# TemperatureSensor.net
KiCad netlist of a schematic drawn in EAGLE
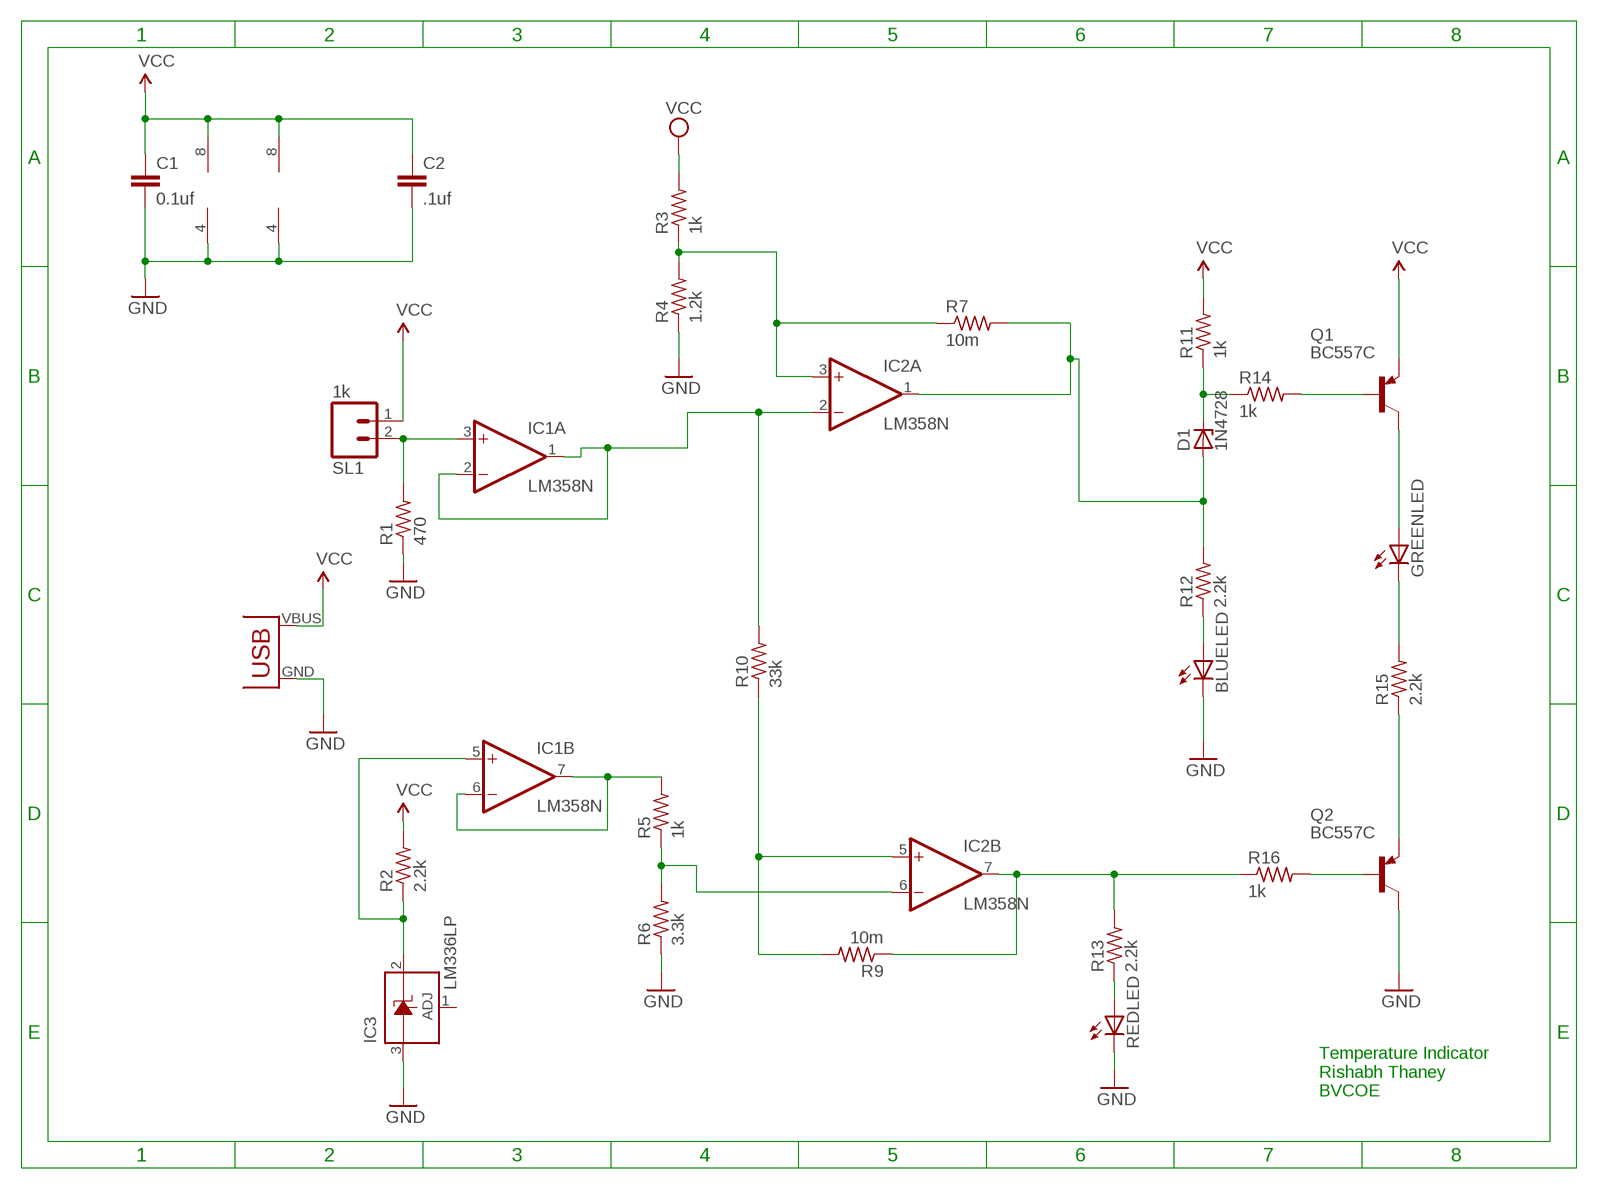
[diagram p0: schematic, sheet 1]

(export (version "E")
  (design (tool "Eeschema 10.0.6"))
  (components
    (comp (ref "BLUELED")
      (value "LED5MM")
      (footprint "eagle-import:LED5MM")
      (libsource (lib "eagle-import") (part "LED5MM"))
    )
    (comp (ref "C1")
      (value "0.1uf")
      (footprint "eagle-import:C025-024X044")
      (libsource (lib "eagle-import") (part "C-EU025-024X044"))
    )
    (comp (ref "C2")
      (value ".1uf")
      (footprint "eagle-import:C025-024X044")
      (libsource (lib "eagle-import") (part "C-EU025-024X044"))
    )
    (comp (ref "D1")
      (value "1N4728")
      (footprint "eagle-import:DO41Z10")
      (libsource (lib "eagle-import") (part "1N4728"))
    )
    (comp (ref "GREENLED")
      (value "LED5MM")
      (footprint "eagle-import:LED5MM")
      (libsource (lib "eagle-import") (part "LED5MM"))
    )
    (comp (ref "IC1")
      (value "LM358N")
      (footprint "eagle-import:DIL08")
      (libsource (lib "eagle-import") (part "LM358N"))
    )
    (comp (ref "IC2")
      (value "LM358N")
      (footprint "eagle-import:DIL08")
      (libsource (lib "eagle-import") (part "LM358N"))
    )
    (comp (ref "IC3")
      (value "LM336LP")
      (footprint "eagle-import:TO92")
      (libsource (lib "eagle-import") (part "LM336LP"))
    )
    (comp (ref "Q1")
      (value "BC557C")
      (footprint "eagle-import:TO92-EBC")
      (libsource (lib "eagle-import") (part "BC557C"))
    )
    (comp (ref "Q2")
      (value "BC557C")
      (footprint "eagle-import:TO92-EBC")
      (libsource (lib "eagle-import") (part "BC557C"))
    )
    (comp (ref "R1")
      (value "470")
      (footprint "eagle-import:0204_7")
      (libsource (lib "eagle-import") (part "R-US_0204/7"))
    )
    (comp (ref "R2")
      (value "2.2k")
      (footprint "eagle-import:0204_7")
      (libsource (lib "eagle-import") (part "R-US_0204/7"))
    )
    (comp (ref "R3")
      (value "1k")
      (footprint "eagle-import:0204_7")
      (libsource (lib "eagle-import") (part "R-US_0204/7"))
    )
    (comp (ref "R4")
      (value "1.2k")
      (footprint "eagle-import:0204_7")
      (libsource (lib "eagle-import") (part "R-US_0204/7"))
    )
    (comp (ref "R5")
      (value "1k")
      (footprint "eagle-import:0204_7")
      (libsource (lib "eagle-import") (part "R-US_0204/7"))
    )
    (comp (ref "R6")
      (value "3.3k")
      (footprint "eagle-import:0204_7")
      (libsource (lib "eagle-import") (part "R-US_0204/7"))
    )
    (comp (ref "R7")
      (value "10m")
      (footprint "eagle-import:0204_7")
      (libsource (lib "eagle-import") (part "R-US_0204/7"))
    )
    (comp (ref "R9")
      (value "10m")
      (footprint "eagle-import:0204_7")
      (libsource (lib "eagle-import") (part "R-US_0204/7"))
    )
    (comp (ref "R10")
      (value "33k")
      (footprint "eagle-import:0204_7")
      (libsource (lib "eagle-import") (part "R-US_0204/7"))
    )
    (comp (ref "R11")
      (value "1k")
      (footprint "eagle-import:0204_7")
      (libsource (lib "eagle-import") (part "R-US_0204/7"))
    )
    (comp (ref "R12")
      (value "2.2k")
      (footprint "eagle-import:0204_7")
      (libsource (lib "eagle-import") (part "R-US_0204/7"))
    )
    (comp (ref "R13")
      (value "2.2k")
      (footprint "eagle-import:0204_7")
      (libsource (lib "eagle-import") (part "R-US_0204/7"))
    )
    (comp (ref "R14")
      (value "1k")
      (footprint "eagle-import:0204_7")
      (libsource (lib "eagle-import") (part "R-US_0204/7"))
    )
    (comp (ref "R15")
      (value "2.2k")
      (footprint "eagle-import:0204_7")
      (libsource (lib "eagle-import") (part "R-US_0204/7"))
    )
    (comp (ref "R16")
      (value "1k")
      (footprint "eagle-import:0204_7")
      (libsource (lib "eagle-import") (part "R-US_0204/7"))
    )
    (comp (ref "REDLED")
      (value "LED5MM")
      (footprint "eagle-import:LED5MM")
      (libsource (lib "eagle-import") (part "LED5MM"))
    )
    (comp (ref "SL1")
      (value "1k")
      (footprint "eagle-import:02P")
      (libsource (lib "eagle-import") (part "M02"))
    )
    (comp (ref "U$1")
      (value "USB(POWER)")
      (footprint "eagle-import:USB(POWER)")
      (libsource (lib "eagle-import") (part "USB(POWER)"))
    )
  )
  (nets
    (net (code "1") (name "GND") (class "Default")
      (node (ref "BLUELED") (pin "K") (pinfunction "C_K") (pintype "passive"))
      (node (ref "C1") (pin "2") (pinfunction "2_2") (pintype "passive"))
      (node (ref "C2") (pin "2") (pinfunction "2_2") (pintype "passive"))
      (node (ref "IC1") (pin "4") (pinfunction "V-_4") (pintype "power_in"))
      (node (ref "IC2") (pin "4") (pinfunction "V-_4") (pintype "power_in"))
      (node (ref "IC3") (pin "3") (pinfunction "A_3") (pintype "input"))
      (node (ref "Q2") (pin "C") (pinfunction "C_C") (pintype "passive"))
      (node (ref "R1") (pin "1") (pinfunction "1_1") (pintype "passive"))
      (node (ref "R4") (pin "1") (pinfunction "1_1") (pintype "passive"))
      (node (ref "R6") (pin "1") (pinfunction "1_1") (pintype "passive"))
      (node (ref "REDLED") (pin "K") (pinfunction "C_K") (pintype "passive"))
      (node (ref "U$1") (pin "GND") (pinfunction "GND_GND") (pintype "power_in"))
    )
    (net (code "2") (name "Net-(BLUELED-PadA)") (class "Default")
      (node (ref "BLUELED") (pin "A") (pinfunction "A_A") (pintype "passive"))
      (node (ref "R12") (pin "1") (pinfunction "1_1") (pintype "passive"))
    )
    (net (code "3") (name "Net-(D1-PadC)") (class "Default")
      (node (ref "D1") (pin "C") (pinfunction "C_C") (pintype "passive"))
      (node (ref "R11") (pin "1") (pinfunction "1_1") (pintype "passive"))
      (node (ref "R14") (pin "1") (pinfunction "1_1") (pintype "passive"))
    )
    (net (code "4") (name "Net-(GREENLED-C)") (class "Default")
      (node (ref "GREENLED") (pin "K") (pinfunction "C_K") (pintype "passive"))
      (node (ref "R15") (pin "2") (pinfunction "2_2") (pintype "passive"))
    )
    (net (code "5") (name "Net-(GREENLED-PadA)") (class "Default")
      (node (ref "GREENLED") (pin "A") (pinfunction "A_A") (pintype "passive"))
      (node (ref "Q1") (pin "C") (pinfunction "C_C") (pintype "passive"))
    )
    (net (code "6") (name "Net-(IC1A-+IN)") (class "Default")
      (node (ref "IC1") (pin "3") (pinfunction "+IN_3") (pintype "input"))
      (node (ref "R1") (pin "2") (pinfunction "2_2") (pintype "passive"))
      (node (ref "SL1") (pin "2") (pinfunction "2_2") (pintype "passive"))
    )
    (net (code "7") (name "Net-(IC1A--IN)") (class "Default")
      (node (ref "IC1") (pin "1") (pinfunction "OUT_1") (pintype "output"))
      (node (ref "IC1") (pin "2") (pinfunction "-IN_2") (pintype "input"))
      (node (ref "IC2") (pin "2") (pinfunction "-IN_2") (pintype "input"))
      (node (ref "R10") (pin "2") (pinfunction "2_2") (pintype "passive"))
    )
    (net (code "8") (name "Net-(IC1B-+IN)") (class "Default")
      (node (ref "IC1") (pin "5") (pinfunction "+IN_5") (pintype "input"))
      (node (ref "IC3") (pin "2") (pinfunction "C_2") (pintype "passive"))
      (node (ref "R2") (pin "1") (pinfunction "1_1") (pintype "passive"))
    )
    (net (code "9") (name "Net-(IC1B--IN)") (class "Default")
      (node (ref "IC1") (pin "6") (pinfunction "-IN_6") (pintype "input"))
      (node (ref "IC1") (pin "7") (pinfunction "OUT_7") (pintype "output"))
      (node (ref "R5") (pin "2") (pinfunction "2_2") (pintype "passive"))
    )
    (net (code "10") (name "Net-(IC2A-+IN)") (class "Default")
      (node (ref "IC2") (pin "3") (pinfunction "+IN_3") (pintype "input"))
      (node (ref "R3") (pin "1") (pinfunction "1_1") (pintype "passive"))
      (node (ref "R4") (pin "2") (pinfunction "2_2") (pintype "passive"))
      (node (ref "R7") (pin "1") (pinfunction "1_1") (pintype "passive"))
    )
    (net (code "11") (name "Net-(IC2A-OUT)") (class "Default")
      (node (ref "D1") (pin "A") (pinfunction "A_A") (pintype "passive"))
      (node (ref "IC2") (pin "1") (pinfunction "OUT_1") (pintype "output"))
      (node (ref "R12") (pin "2") (pinfunction "2_2") (pintype "passive"))
      (node (ref "R7") (pin "2") (pinfunction "2_2") (pintype "passive"))
    )
    (net (code "12") (name "Net-(IC2B-+IN)") (class "Default")
      (node (ref "IC2") (pin "5") (pinfunction "+IN_5") (pintype "input"))
      (node (ref "R10") (pin "1") (pinfunction "1_1") (pintype "passive"))
      (node (ref "R9") (pin "2") (pinfunction "2_2") (pintype "passive"))
    )
    (net (code "13") (name "Net-(IC2B--IN)") (class "Default")
      (node (ref "IC2") (pin "6") (pinfunction "-IN_6") (pintype "input"))
      (node (ref "R5") (pin "1") (pinfunction "1_1") (pintype "passive"))
      (node (ref "R6") (pin "2") (pinfunction "2_2") (pintype "passive"))
    )
    (net (code "14") (name "Net-(IC2B-OUT)") (class "Default")
      (node (ref "IC2") (pin "7") (pinfunction "OUT_7") (pintype "output"))
      (node (ref "R13") (pin "2") (pinfunction "2_2") (pintype "passive"))
      (node (ref "R16") (pin "1") (pinfunction "1_1") (pintype "passive"))
      (node (ref "R9") (pin "1") (pinfunction "1_1") (pintype "passive"))
    )
    (net (code "15") (name "Net-(Q1-PadB)") (class "Default")
      (node (ref "Q1") (pin "B") (pinfunction "B_B") (pintype "passive"))
      (node (ref "R14") (pin "2") (pinfunction "2_2") (pintype "passive"))
    )
    (net (code "16") (name "Net-(Q2-PadB)") (class "Default")
      (node (ref "Q2") (pin "B") (pinfunction "B_B") (pintype "passive"))
      (node (ref "R16") (pin "2") (pinfunction "2_2") (pintype "passive"))
    )
    (net (code "17") (name "Net-(Q2-PadE)") (class "Default")
      (node (ref "Q2") (pin "E") (pinfunction "E_E") (pintype "passive"))
      (node (ref "R15") (pin "1") (pinfunction "1_1") (pintype "passive"))
    )
    (net (code "18") (name "Net-(R13-Pad1)") (class "Default")
      (node (ref "R13") (pin "1") (pinfunction "1_1") (pintype "passive"))
      (node (ref "REDLED") (pin "A") (pinfunction "A_A") (pintype "passive"))
    )
    (net (code "19") (name "VCC") (class "Default")
      (node (ref "C1") (pin "1") (pinfunction "1_1") (pintype "passive"))
      (node (ref "C2") (pin "1") (pinfunction "1_1") (pintype "passive"))
      (node (ref "IC1") (pin "8") (pinfunction "V+_8") (pintype "power_in"))
      (node (ref "IC2") (pin "8") (pinfunction "V+_8") (pintype "power_in"))
      (node (ref "Q1") (pin "E") (pinfunction "E_E") (pintype "passive"))
      (node (ref "R11") (pin "2") (pinfunction "2_2") (pintype "passive"))
      (node (ref "R2") (pin "2") (pinfunction "2_2") (pintype "passive"))
      (node (ref "R3") (pin "2") (pinfunction "2_2") (pintype "passive"))
      (node (ref "SL1") (pin "1") (pinfunction "1_1") (pintype "passive"))
      (node (ref "U$1") (pin "VBUS") (pinfunction "VCC_VBUS") (pintype "power_in"))
    )
    (net (code "20") (name "unconnected-(IC3-ADJ-Pad1)") (class "Default")
      (node (ref "IC3") (pin "1") (pinfunction "ADJ_1") (pintype "input"))
    )
  )
)
